# NusbioMCU_NeoPixels.net
KiCad netlist of a schematic drawn in EAGLE
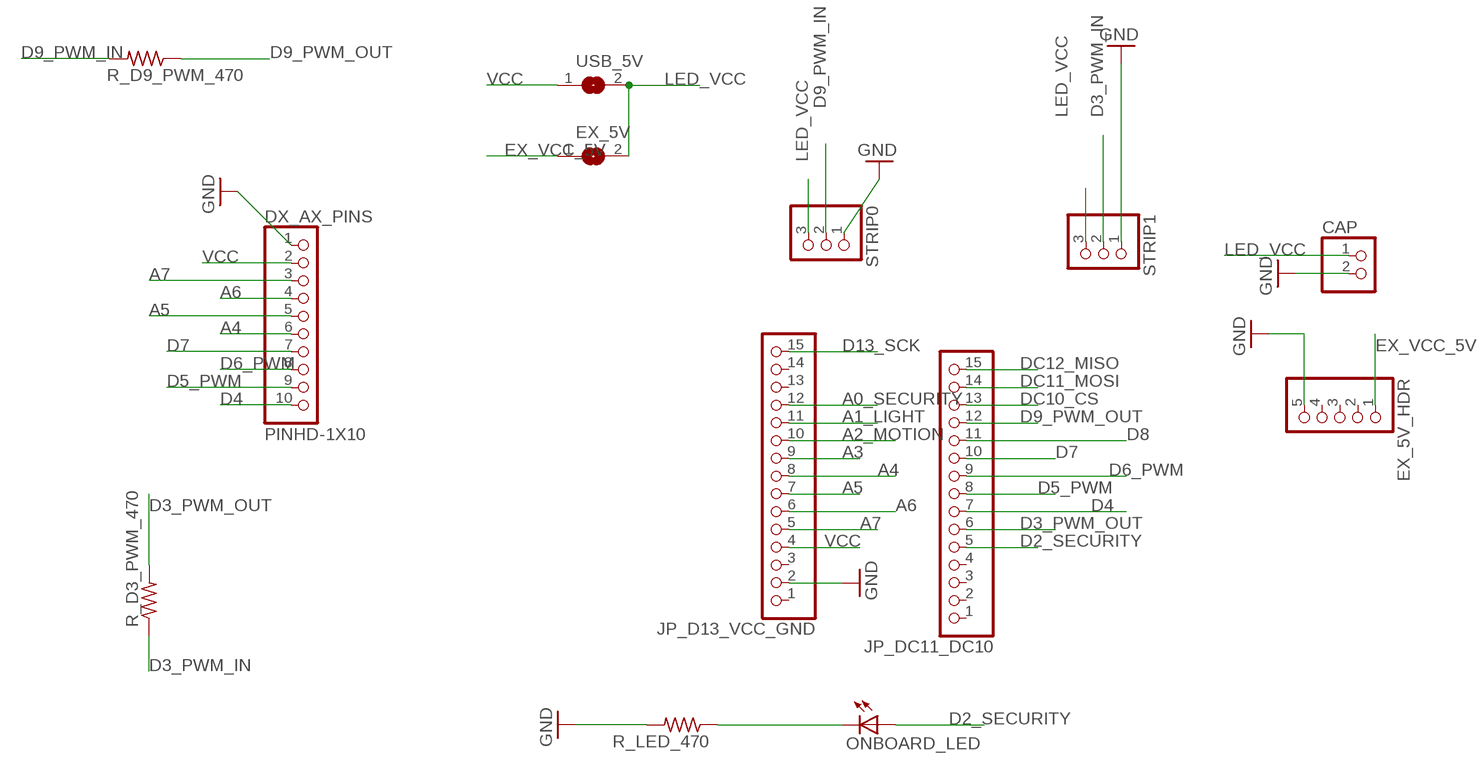
[diagram p0: schematic, sheet 1]

(export (version "E")
  (design (tool "Eeschema 10.0.6"))
  (components
    (comp (ref "CAP")
      (value "PINHD-1X2")
      (footprint "eagle-import:1X02")
      (libsource (lib "eagle-import") (part "PINHD-1X2"))
    )
    (comp (ref "DX_AX_PINS")
      (value "PINHD-1X10")
      (footprint "eagle-import:1X10-BIG")
      (libsource (lib "eagle-import") (part "PINHD-1X10"))
    )
    (comp (ref "EX_5V")
      (value "SOLDERJUMPERREFLOW")
      (footprint "eagle-import:SOLDERJUMPER_REFLOW")
      (libsource (lib "eagle-import") (part "SOLDERJUMPERREFLOW"))
    )
    (comp (ref "EX_5V_HDR")
      (value "PINHD-1X5")
      (footprint "eagle-import:1X05")
      (libsource (lib "eagle-import") (part "PINHD-1X5"))
    )
    (comp (ref "JP_D13_VCC_GND")
      (value "PINHD-1X15")
      (footprint "eagle-import:1X15")
      (libsource (lib "eagle-import") (part "PINHD-1X15"))
    )
    (comp (ref "JP_DC11_DC10")
      (value "PINHD-1X15")
      (footprint "eagle-import:1X15")
      (libsource (lib "eagle-import") (part "PINHD-1X15"))
    )
    (comp (ref "ONBOARD_LED")
      (value "LEDSMT1206")
      (footprint "eagle-import:1206")
      (libsource (lib "eagle-import") (part "LEDSMT1206"))
    )
    (comp (ref "R_D3_PWM_470")
      (value "R-US_R1206")
      (footprint "eagle-import:R1206")
      (libsource (lib "eagle-import") (part "R-US_R1206"))
    )
    (comp (ref "R_D9_PWM_470")
      (value "R-US_R1206")
      (footprint "eagle-import:R1206")
      (libsource (lib "eagle-import") (part "R-US_R1206"))
    )
    (comp (ref "R_LED_470")
      (value "R-US_R1206")
      (footprint "eagle-import:R1206")
      (libsource (lib "eagle-import") (part "R-US_R1206"))
    )
    (comp (ref "STRIP0")
      (value "PINHD-1X3")
      (footprint "eagle-import:1X03")
      (libsource (lib "eagle-import") (part "PINHD-1X3"))
    )
    (comp (ref "STRIP1")
      (value "PINHD-1X3")
      (footprint "eagle-import:1X03")
      (libsource (lib "eagle-import") (part "PINHD-1X3"))
    )
    (comp (ref "USB_5V")
      (value "SOLDERJUMPERREFLOW")
      (footprint "eagle-import:SOLDERJUMPER_REFLOW")
      (libsource (lib "eagle-import") (part "SOLDERJUMPERREFLOW"))
    )
  )
  (nets
    (net (code "1") (name "/A0_SECURITY") (class "Default")
      (node (ref "JP_D13_VCC_GND") (pin "12") (pinfunction "12_12") (pintype "passive"))
    )
    (net (code "2") (name "/A1_LIGHT") (class "Default")
      (node (ref "JP_D13_VCC_GND") (pin "11") (pinfunction "11_11") (pintype "passive"))
    )
    (net (code "3") (name "/A2_MOTION") (class "Default")
      (node (ref "JP_D13_VCC_GND") (pin "10") (pinfunction "10_10") (pintype "passive"))
    )
    (net (code "4") (name "/A3") (class "Default")
      (node (ref "JP_D13_VCC_GND") (pin "9") (pinfunction "9_9") (pintype "passive"))
    )
    (net (code "5") (name "/A4") (class "Default")
      (node (ref "DX_AX_PINS") (pin "6") (pinfunction "6_6") (pintype "passive"))
      (node (ref "JP_D13_VCC_GND") (pin "8") (pinfunction "8_8") (pintype "passive"))
    )
    (net (code "6") (name "/A5") (class "Default")
      (node (ref "DX_AX_PINS") (pin "5") (pinfunction "5_5") (pintype "passive"))
      (node (ref "JP_D13_VCC_GND") (pin "7") (pinfunction "7_7") (pintype "passive"))
    )
    (net (code "7") (name "/A6") (class "Default")
      (node (ref "DX_AX_PINS") (pin "4") (pinfunction "4_4") (pintype "passive"))
      (node (ref "JP_D13_VCC_GND") (pin "6") (pinfunction "6_6") (pintype "passive"))
    )
    (net (code "8") (name "/A7") (class "Default")
      (node (ref "DX_AX_PINS") (pin "3") (pinfunction "3_3") (pintype "passive"))
      (node (ref "JP_D13_VCC_GND") (pin "5") (pinfunction "5_5") (pintype "passive"))
    )
    (net (code "9") (name "/D2_SECURITY") (class "Default")
      (node (ref "JP_DC11_DC10") (pin "5") (pinfunction "5_5") (pintype "passive"))
      (node (ref "ONBOARD_LED") (pin "A") (pinfunction "A_A") (pintype "passive"))
    )
    (net (code "10") (name "/D3_PWM_IN") (class "Default")
      (node (ref "R_D3_PWM_470") (pin "1") (pinfunction "1_1") (pintype "passive"))
      (node (ref "STRIP1") (pin "2") (pinfunction "2_2") (pintype "passive"))
    )
    (net (code "11") (name "/D3_PWM_OUT") (class "Default")
      (node (ref "JP_DC11_DC10") (pin "6") (pinfunction "6_6") (pintype "passive"))
      (node (ref "R_D3_PWM_470") (pin "2") (pinfunction "2_2") (pintype "passive"))
    )
    (net (code "12") (name "/D4") (class "Default")
      (node (ref "DX_AX_PINS") (pin "10") (pinfunction "10_10") (pintype "passive"))
      (node (ref "JP_DC11_DC10") (pin "7") (pinfunction "7_7") (pintype "passive"))
    )
    (net (code "13") (name "/D5_PWM") (class "Default")
      (node (ref "DX_AX_PINS") (pin "9") (pinfunction "9_9") (pintype "passive"))
      (node (ref "JP_DC11_DC10") (pin "8") (pinfunction "8_8") (pintype "passive"))
    )
    (net (code "14") (name "/D6_PWM") (class "Default")
      (node (ref "DX_AX_PINS") (pin "8") (pinfunction "8_8") (pintype "passive"))
      (node (ref "JP_DC11_DC10") (pin "9") (pinfunction "9_9") (pintype "passive"))
    )
    (net (code "15") (name "/D7") (class "Default")
      (node (ref "DX_AX_PINS") (pin "7") (pinfunction "7_7") (pintype "passive"))
      (node (ref "JP_DC11_DC10") (pin "10") (pinfunction "10_10") (pintype "passive"))
    )
    (net (code "16") (name "/D8") (class "Default")
      (node (ref "JP_DC11_DC10") (pin "11") (pinfunction "11_11") (pintype "passive"))
    )
    (net (code "17") (name "/D9_PWM_IN") (class "Default")
      (node (ref "R_D9_PWM_470") (pin "2") (pinfunction "2_2") (pintype "passive"))
      (node (ref "STRIP0") (pin "2") (pinfunction "2_2") (pintype "passive"))
    )
    (net (code "18") (name "/D9_PWM_OUT") (class "Default")
      (node (ref "JP_DC11_DC10") (pin "12") (pinfunction "12_12") (pintype "passive"))
      (node (ref "R_D9_PWM_470") (pin "1") (pinfunction "1_1") (pintype "passive"))
    )
    (net (code "19") (name "/D13_SCK") (class "Default")
      (node (ref "JP_D13_VCC_GND") (pin "15") (pinfunction "15_15") (pintype "passive"))
    )
    (net (code "20") (name "/DC10_CS") (class "Default")
      (node (ref "JP_DC11_DC10") (pin "13") (pinfunction "13_13") (pintype "passive"))
    )
    (net (code "21") (name "/DC11_MOSI") (class "Default")
      (node (ref "JP_DC11_DC10") (pin "14") (pinfunction "14_14") (pintype "passive"))
    )
    (net (code "22") (name "/DC12_MISO") (class "Default")
      (node (ref "JP_DC11_DC10") (pin "15") (pinfunction "15_15") (pintype "passive"))
    )
    (net (code "23") (name "/EX_VCC_5V") (class "Default")
      (node (ref "EX_5V") (pin "1") (pinfunction "1_1") (pintype "passive"))
      (node (ref "EX_5V_HDR") (pin "1") (pinfunction "1_1") (pintype "passive"))
    )
    (net (code "24") (name "/LED_VCC") (class "Default")
      (node (ref "CAP") (pin "1") (pinfunction "1_1") (pintype "passive"))
      (node (ref "EX_5V") (pin "2") (pinfunction "2_2") (pintype "passive"))
      (node (ref "STRIP0") (pin "3") (pinfunction "3_3") (pintype "passive"))
      (node (ref "STRIP1") (pin "3") (pinfunction "3_3") (pintype "passive"))
      (node (ref "USB_5V") (pin "2") (pinfunction "2_2") (pintype "passive"))
    )
    (net (code "25") (name "/VCC") (class "Default")
      (node (ref "DX_AX_PINS") (pin "2") (pinfunction "2_2") (pintype "passive"))
      (node (ref "JP_D13_VCC_GND") (pin "4") (pinfunction "4_4") (pintype "passive"))
      (node (ref "USB_5V") (pin "1") (pinfunction "1_1") (pintype "passive"))
    )
    (net (code "26") (name "GND") (class "Default")
      (node (ref "CAP") (pin "2") (pinfunction "2_2") (pintype "passive"))
      (node (ref "DX_AX_PINS") (pin "1") (pinfunction "1_1") (pintype "passive"))
      (node (ref "EX_5V_HDR") (pin "5") (pinfunction "5_5") (pintype "passive"))
      (node (ref "JP_D13_VCC_GND") (pin "2") (pinfunction "2_2") (pintype "passive"))
      (node (ref "R_LED_470") (pin "2") (pinfunction "2_2") (pintype "passive"))
      (node (ref "STRIP0") (pin "1") (pinfunction "1_1") (pintype "passive"))
      (node (ref "STRIP1") (pin "1") (pinfunction "1_1") (pintype "passive"))
    )
    (net (code "27") (name "Net-(ONBOARD_LED-PadC)") (class "Default")
      (node (ref "ONBOARD_LED") (pin "C") (pinfunction "C_C") (pintype "passive"))
      (node (ref "R_LED_470") (pin "1") (pinfunction "1_1") (pintype "passive"))
    )
    (net (code "28") (name "unconnected-(EX_5V_HDR-Pad2)") (class "Default")
      (node (ref "EX_5V_HDR") (pin "2") (pinfunction "2_2") (pintype "passive"))
    )
    (net (code "29") (name "unconnected-(EX_5V_HDR-Pad3)") (class "Default")
      (node (ref "EX_5V_HDR") (pin "3") (pinfunction "3_3") (pintype "passive"))
    )
    (net (code "30") (name "unconnected-(EX_5V_HDR-Pad4)") (class "Default")
      (node (ref "EX_5V_HDR") (pin "4") (pinfunction "4_4") (pintype "passive"))
    )
    (net (code "31") (name "unconnected-(JP_D13_VCC_GND-Pad1)") (class "Default")
      (node (ref "JP_D13_VCC_GND") (pin "1") (pinfunction "1_1") (pintype "passive"))
    )
    (net (code "32") (name "unconnected-(JP_D13_VCC_GND-Pad3)") (class "Default")
      (node (ref "JP_D13_VCC_GND") (pin "3") (pinfunction "3_3") (pintype "passive"))
    )
    (net (code "33") (name "unconnected-(JP_D13_VCC_GND-Pad13)") (class "Default")
      (node (ref "JP_D13_VCC_GND") (pin "13") (pinfunction "13_13") (pintype "passive"))
    )
    (net (code "34") (name "unconnected-(JP_D13_VCC_GND-Pad14)") (class "Default")
      (node (ref "JP_D13_VCC_GND") (pin "14") (pinfunction "14_14") (pintype "passive"))
    )
    (net (code "35") (name "unconnected-(JP_DC11_DC10-Pad1)") (class "Default")
      (node (ref "JP_DC11_DC10") (pin "1") (pinfunction "1_1") (pintype "passive"))
    )
    (net (code "36") (name "unconnected-(JP_DC11_DC10-Pad2)") (class "Default")
      (node (ref "JP_DC11_DC10") (pin "2") (pinfunction "2_2") (pintype "passive"))
    )
    (net (code "37") (name "unconnected-(JP_DC11_DC10-Pad3)") (class "Default")
      (node (ref "JP_DC11_DC10") (pin "3") (pinfunction "3_3") (pintype "passive"))
    )
    (net (code "38") (name "unconnected-(JP_DC11_DC10-Pad4)") (class "Default")
      (node (ref "JP_DC11_DC10") (pin "4") (pinfunction "4_4") (pintype "passive"))
    )
  )
)
